# Inertial_Measurement_RTC.net
KiCad netlist of a schematic drawn in Altium Designer
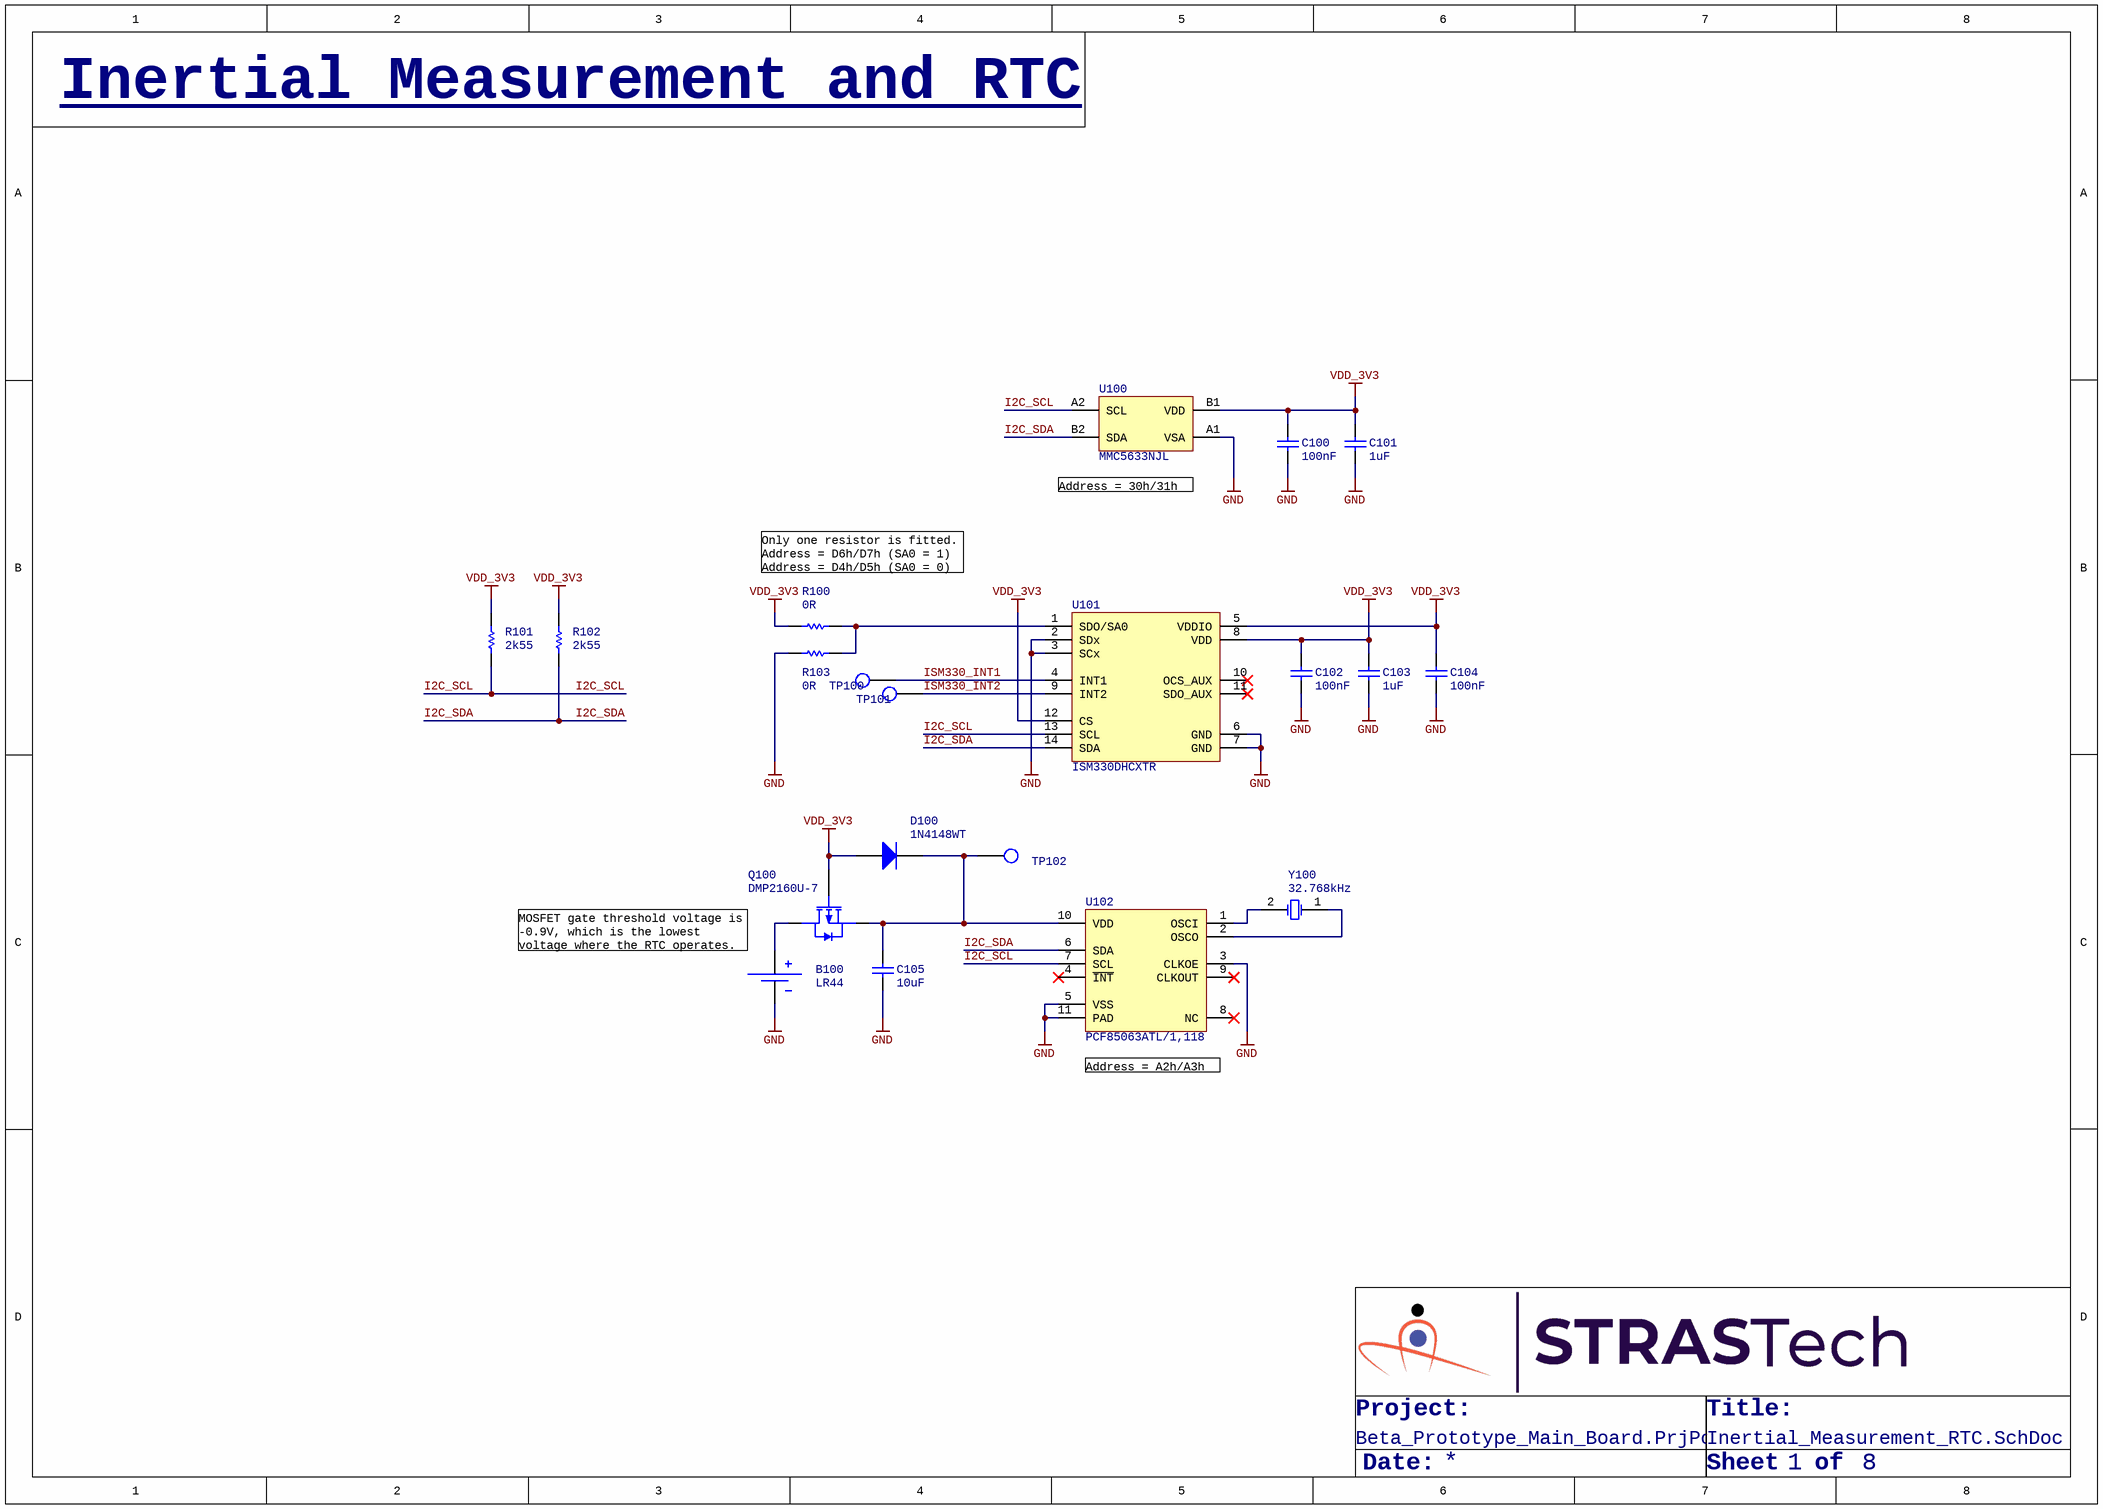
[diagram p0: Inertial_Measurement_RTC.SchDoc]

(export (version "E")
  (design (tool "Eeschema 10.0.6"))
  (components
    (comp (ref "B100")
      (value "LR44")
      (footprint "Holder,Cell,LR44,PCB,Thru")
      (description "Battery Retainer Coin, 11.6mm 1 Cell PC Pin")
      (fields
        (field (name "MANUFACTURER") "Keystone Electronics")
        (field (name "MANUFACTURER PART NUMBER") "2997")
        (field (name "CREATEDBY") "Judd Foster")
      )
      (libsource (lib "symbols") (part "Holder,Cell,LR44,PCB,Thru"))
    )
    (comp (ref "C100")
      (value "100nF")
      (footprint "Cap,SMD,0402")
      (description "0.1µF ±10% 25V Ceramic Capacitor X7R 0402 (1005 Metric)")
      (fields
        (field (name "VENDOR PART NUMBER") "490-14603-1-ND")
        (field (name "MANUFACTURER") "Murata Electronics")
        (field (name "CREATEDBY") "Judd Foster")
      )
      (libsource (lib "symbols") (part "CAP,Cer,100nF,25VDC,X7R,0402"))
    )
    (comp (ref "C101")
      (value "1uF")
      (footprint "Cap,SMD,0402")
      (description "1 µF ±10% 35V Ceramic Capacitor X5R 0402 (1005 Metric)")
      (fields
        (field (name "VENDOR PART NUMBER") "445-9073-1-ND")
        (field (name "MANUFACTURER") "TDK Corporation")
        (field (name "CREATEDBY") "Judd Foster")
      )
      (libsource (lib "symbols") (part "CAP,Cer,1uF,35VDC,X5R,0402"))
    )
    (comp (ref "C102")
      (value "100nF")
      (footprint "Cap,SMD,0402")
      (description "0.1µF ±10% 25V Ceramic Capacitor X7R 0402 (1005 Metric)")
      (fields
        (field (name "VENDOR PART NUMBER") "490-14603-1-ND")
        (field (name "MANUFACTURER") "Murata Electronics")
        (field (name "CREATEDBY") "Judd Foster")
      )
      (libsource (lib "symbols") (part "CAP,Cer,100nF,25VDC,X7R,0402"))
    )
    (comp (ref "C103")
      (value "1uF")
      (footprint "Cap,SMD,0402")
      (description "1 µF ±10% 35V Ceramic Capacitor X5R 0402 (1005 Metric)")
      (fields
        (field (name "VENDOR PART NUMBER") "445-9073-1-ND")
        (field (name "MANUFACTURER") "TDK Corporation")
        (field (name "CREATEDBY") "Judd Foster")
      )
      (libsource (lib "symbols") (part "CAP,Cer,1uF,35VDC,X5R,0402"))
    )
    (comp (ref "C104")
      (value "100nF")
      (footprint "Cap,SMD,0402")
      (description "0.1µF ±10% 25V Ceramic Capacitor X7R 0402 (1005 Metric)")
      (fields
        (field (name "VENDOR PART NUMBER") "490-14603-1-ND")
        (field (name "MANUFACTURER") "Murata Electronics")
        (field (name "CREATEDBY") "Judd Foster")
      )
      (libsource (lib "symbols") (part "CAP,Cer,100nF,25VDC,X7R,0402"))
    )
    (comp (ref "C105")
      (value "10uF")
      (footprint "Cap,SMD,0402")
      (description "10 µF ±20% 10V Ceramic Capacitor X5R 0402 (1005 Metric)")
      (fields
        (field (name "VENDOR PART NUMBER") "1276-1450-1-ND")
        (field (name "MANUFACTURER") "Samsung Electro-Mechanics")
        (field (name "CREATEDBY") "Judd Foster")
      )
      (libsource (lib "symbols") (part "CAP,Cer,10uF,10VDC,X5R,0402"))
    )
    (comp (ref "D100")
      (value "1N4148WT")
      (footprint "SOD523")
      (description "Diode Standard 75 V 200mA Surface Mount SOD-523F")
      (fields
        (field (name "MANUFACTURER") "ON Semiconductor")
        (field (name "VENDOR PART NUMBER") "1N4148WTCT-ND")
        (field (name "CREATEDBY") "Judd Foster")
      )
      (libsource (lib "symbols") (part "DIODE,Gen,75V,200mA,SOD523F"))
    )
    (comp (ref "Q100")
      (value "DMP2160U-7")
      (footprint "SOT23-3")
      (description "P-Channel 20 V 3.2A (Ta) 1.4W (Ta) Surface Mount SOT-23-3")
      (fields
        (field (name "MANUFACTURER") "Diodes Incorporated")
        (field (name "VENDOR PART NUMBER") "DMP2160UDICT-ND")
        (field (name "CREATEDBY") "Judd Foster")
      )
      (libsource (lib "symbols") (part "MOSFET,P Ch,20V,3.2A"))
    )
    (comp (ref "R100")
      (value "0R")
      (footprint "RES,0402")
      (description "0 Ohms Jumper 0.1W, 1/10W Chip Resistor 0402 (1005 Metric) Automotive AEC-Q200 Thick Film")
      (fields
        (field (name "MANUFACTURER") "Panasonic Electronic Components")
        (field (name "MANUFACTURER PART NUMBER") "ERJ-2GE0R00X")
        (field (name "CREATEDBY") "Judd Foster")
      )
      (libsource (lib "symbols") (part "RES,0R0,0.1W,0402"))
    )
    (comp (ref "R101")
      (value "2k55")
      (footprint "RES,0402")
      (description "2.55 kOhms ±1% 0.063W, 1/16W Chip Resistor 0402 (1005 Metric) Automotive AEC-Q200 Thick Film")
      (fields
        (field (name "MANUFACTURER") "Stackpole Electronics Inc")
        (field (name "MANUFACTURER PART NUMBER") "RMCF0402FT2K55")
        (field (name "CREATEDBY") "Judd Foster")
      )
      (libsource (lib "symbols") (part "RES,2k55,1%,0.063W,0402"))
    )
    (comp (ref "R102")
      (value "2k55")
      (footprint "RES,0402")
      (description "2.55 kOhms ±1% 0.063W, 1/16W Chip Resistor 0402 (1005 Metric) Automotive AEC-Q200 Thick Film")
      (fields
        (field (name "MANUFACTURER") "Stackpole Electronics Inc")
        (field (name "MANUFACTURER PART NUMBER") "RMCF0402FT2K55")
        (field (name "CREATEDBY") "Judd Foster")
      )
      (libsource (lib "symbols") (part "RES,2k55,1%,0.063W,0402"))
    )
    (comp (ref "R103")
      (value "0R")
      (footprint "RES,0402")
      (description "0 Ohms Jumper 0.1W, 1/10W Chip Resistor 0402 (1005 Metric) Automotive AEC-Q200 Thick Film")
      (fields
        (field (name "MANUFACTURER") "Panasonic Electronic Components")
        (field (name "MANUFACTURER PART NUMBER") "ERJ-2GE0R00X")
        (field (name "CREATEDBY") "Judd Foster")
      )
      (libsource (lib "symbols") (part "RES,0R0,0.1W,0402"))
    )
    (comp (ref "TP100")
      (value "TESTPOINT")
      (footprint "testpoint,smd,round,1mm")
      (description "PCB Testpoint")
      (fields (field (name "CREATEDBY") "Judd Foster"))
      (libsource (lib "symbols") (part "TESTPOINT"))
    )
    (comp (ref "TP101")
      (value "TESTPOINT")
      (footprint "testpoint,smd,round,1mm")
      (description "PCB Testpoint")
      (fields (field (name "CREATEDBY") "Judd Foster"))
      (libsource (lib "symbols") (part "TESTPOINT"))
    )
    (comp (ref "TP102")
      (value "TESTPOINT")
      (footprint "testpoint,smd,round,1mm")
      (description "PCB Testpoint")
      (fields (field (name "CREATEDBY") "Judd Foster"))
      (libsource (lib "symbols") (part "TESTPOINT"))
    )
    (comp (ref "U100")
      (value "MMC5633NJL")
      (footprint "IC,WLP,2x2,P0.4mm")
      (description "Magnetoresistive Sensor X, Y, Z Axis 4-WLP (0.85x0.85)")
      (fields
        (field (name "MANUFACTURER") "Memsic Inc.")
        (field (name "VENDOR PART NUMBER") "1267-MMC5633NJLCT-ND")
        (field (name "CREATEDBY") "Judd Foster")
      )
      (libsource (lib "symbols") (part "MMC5633NJL"))
    )
    (comp (ref "U101")
      (value "ISM330DHCXTR")
      (footprint "IC,LGA-14L,2.5x3mm")
      (description "Accelerometer, Gyroscope, Temperature, 6 Axis Sensor I²C, SPI Output")
      (fields
        (field (name "MANUFACTURER") "STMicroelectronics")
        (field (name "VENDOR PART NUMBER") "497-19784-1-ND")
        (field (name "CREATEDBY") "Judd Foster")
      )
      (libsource (lib "symbols") (part "ISM330DHCXTR"))
    )
    (comp (ref "U102")
      (value "PCF85063ATL/1,118")
      (footprint "IC,DFN-10_3x3,P0.5mm")
      (description "Real Time Clock (RTC) IC Clock/Calendar - I²C, 2-Wire Serial 10-XFDFN Exposed Pad")
      (fields
        (field (name "MANUFACTURER") "NXP USA Inc.")
        (field (name "VENDOR PART NUMBER") "568-10235-1-ND")
        (field (name "CREATEDBY") "Judd Foster")
      )
      (libsource (lib "symbols") (part "PCF85063ATL/1,118"))
    )
    (comp (ref "Y100")
      (value "32.768kHz")
      (footprint "XTAL,SMD,2PIN,2.0x1.2MM")
      (description "32.768 kHz ±20ppm Crystal 9pF 70 kOhms 2-SMD, No Lead")
      (fields
        (field (name "MANUFACTURER") "Micro Crystal AG")
        (field (name "MANUFACTURER PART NUMBER") "CM8V-T1A-32.768KHZ-9PF-20PPM-TA-QC")
        (field (name "CREATEDBY") "Judd Foster")
      )
      (libsource (lib "symbols") (part "XTAL,32.768kHz,9pF,SMD"))
    )
  )
  (nets
    (net (code "1") (name "/I2C_SCL") (class "Default")
      (node (ref "R101") (pin "1") (pinfunction "1_1") (pintype "passive"))
      (node (ref "U100") (pin "A2") (pinfunction "SCL_A2") (pintype "passive"))
      (node (ref "U101") (pin "13") (pinfunction "SCL_13") (pintype "passive"))
      (node (ref "U102") (pin "7") (pinfunction "SCL_7") (pintype "passive"))
    )
    (net (code "2") (name "/I2C_SDA") (class "Default")
      (node (ref "R102") (pin "1") (pinfunction "1_1") (pintype "passive"))
      (node (ref "U100") (pin "B2") (pinfunction "SDA_B2") (pintype "passive"))
      (node (ref "U101") (pin "14") (pinfunction "SDA_14") (pintype "passive"))
      (node (ref "U102") (pin "6") (pinfunction "SDA_6") (pintype "passive"))
    )
    (net (code "3") (name "/ISM330_INT1") (class "Default")
      (node (ref "TP100") (pin "1") (pinfunction "TP_1") (pintype "passive"))
      (node (ref "U101") (pin "4") (pinfunction "INT1_4") (pintype "passive"))
    )
    (net (code "4") (name "/ISM330_INT2") (class "Default")
      (node (ref "TP101") (pin "1") (pinfunction "TP_1") (pintype "passive"))
      (node (ref "U101") (pin "9") (pinfunction "INT2_9") (pintype "passive"))
    )
    (net (code "5") (name "GND") (class "Default")
      (node (ref "B100") (pin "2") (pinfunction "BATT_N_2") (pintype "passive"))
      (node (ref "C100") (pin "2") (pinfunction "2_2") (pintype "passive"))
      (node (ref "C101") (pin "1") (pinfunction "1_1") (pintype "passive"))
      (node (ref "C102") (pin "1") (pinfunction "1_1") (pintype "passive"))
      (node (ref "C103") (pin "1") (pinfunction "1_1") (pintype "passive"))
      (node (ref "C104") (pin "1") (pinfunction "1_1") (pintype "passive"))
      (node (ref "C105") (pin "2") (pinfunction "2_2") (pintype "passive"))
      (node (ref "R103") (pin "1") (pinfunction "1_1") (pintype "passive"))
      (node (ref "U100") (pin "A1") (pinfunction "VSA_A1") (pintype "passive"))
      (node (ref "U101") (pin "2") (pinfunction "SDx_2") (pintype "passive"))
      (node (ref "U101") (pin "3") (pinfunction "SCx_3") (pintype "passive"))
      (node (ref "U101") (pin "6") (pinfunction "GND_6") (pintype "passive"))
      (node (ref "U101") (pin "7") (pinfunction "GND_7") (pintype "passive"))
      (node (ref "U102") (pin "11") (pinfunction "PAD_11") (pintype "passive"))
      (node (ref "U102") (pin "3") (pinfunction "CLKOE_3") (pintype "passive"))
      (node (ref "U102") (pin "5") (pinfunction "VSS_5") (pintype "passive"))
    )
    (net (code "6") (name "Net-(B100-BATT_P)") (class "Default")
      (node (ref "B100") (pin "1") (pinfunction "BATT_P_1") (pintype "passive"))
      (node (ref "Q100") (pin "3") (pinfunction "D_3") (pintype "passive"))
    )
    (net (code "7") (name "Net-(D100-K)") (class "Default")
      (node (ref "C105") (pin "1") (pinfunction "1_1") (pintype "passive"))
      (node (ref "D100") (pin "1") (pinfunction "K_1") (pintype "passive"))
      (node (ref "Q100") (pin "2") (pinfunction "S_2") (pintype "passive"))
      (node (ref "TP102") (pin "1") (pinfunction "TP_1") (pintype "passive"))
      (node (ref "U102") (pin "10") (pinfunction "VDD_10") (pintype "passive"))
    )
    (net (code "8") (name "Net-(U101-SDO{slash}SA0)") (class "Default")
      (node (ref "R100") (pin "2") (pinfunction "2_2") (pintype "passive"))
      (node (ref "R103") (pin "2") (pinfunction "2_2") (pintype "passive"))
      (node (ref "U101") (pin "1") (pinfunction "SDO/SA0_1") (pintype "passive"))
    )
    (net (code "9") (name "Net-(U102-OSCI)") (class "Default")
      (node (ref "U102") (pin "1") (pinfunction "OSCI_1") (pintype "passive"))
      (node (ref "Y100") (pin "2") (pinfunction "GND_2") (pintype "passive"))
    )
    (net (code "10") (name "Net-(U102-OSCO)") (class "Default")
      (node (ref "U102") (pin "2") (pinfunction "OSCO_2") (pintype "passive"))
      (node (ref "Y100") (pin "1") (pinfunction "OSC1_1") (pintype "passive"))
    )
    (net (code "11") (name "VDD_3V3") (class "Default")
      (node (ref "C100") (pin "1") (pinfunction "1_1") (pintype "passive"))
      (node (ref "C101") (pin "2") (pinfunction "2_2") (pintype "passive"))
      (node (ref "C102") (pin "2") (pinfunction "2_2") (pintype "passive"))
      (node (ref "C103") (pin "2") (pinfunction "2_2") (pintype "passive"))
      (node (ref "C104") (pin "2") (pinfunction "2_2") (pintype "passive"))
      (node (ref "D100") (pin "2") (pinfunction "A_2") (pintype "passive"))
      (node (ref "Q100") (pin "1") (pinfunction "G_1") (pintype "passive"))
      (node (ref "R100") (pin "1") (pinfunction "1_1") (pintype "passive"))
      (node (ref "R101") (pin "2") (pinfunction "2_2") (pintype "passive"))
      (node (ref "R102") (pin "2") (pinfunction "2_2") (pintype "passive"))
      (node (ref "U100") (pin "B1") (pinfunction "VDD_B1") (pintype "passive"))
      (node (ref "U101") (pin "12") (pinfunction "CS_12") (pintype "passive"))
      (node (ref "U101") (pin "5") (pinfunction "VDDIO_5") (pintype "passive"))
      (node (ref "U101") (pin "8") (pinfunction "VDD_8") (pintype "passive"))
    )
    (net (code "12") (name "unconnected-(U101-OCS_AUX-Pad10)") (class "Default")
      (node (ref "U101") (pin "10") (pinfunction "OCS_AUX_10") (pintype "passive+no_connect"))
    )
    (net (code "13") (name "unconnected-(U101-SDO_AUX-Pad11)") (class "Default")
      (node (ref "U101") (pin "11") (pinfunction "SDO_AUX_11") (pintype "passive+no_connect"))
    )
    (net (code "14") (name "unconnected-(U102-CLKOUT-Pad9)") (class "Default")
      (node (ref "U102") (pin "9") (pinfunction "CLKOUT_9") (pintype "passive+no_connect"))
    )
    (net (code "15") (name "unconnected-(U102-NC-Pad8)") (class "Default")
      (node (ref "U102") (pin "8") (pinfunction "NC_8") (pintype "passive+no_connect"))
    )
    (net (code "16") (name "unconnected-(U102-~{INT}-Pad4)") (class "Default")
      (node (ref "U102") (pin "4") (pinfunction "~{INT}_4") (pintype "passive+no_connect"))
    )
  )
)
